# XMOS_TSBOARD_SPDIF.net
KiCad netlist of a schematic drawn in Altium Designer
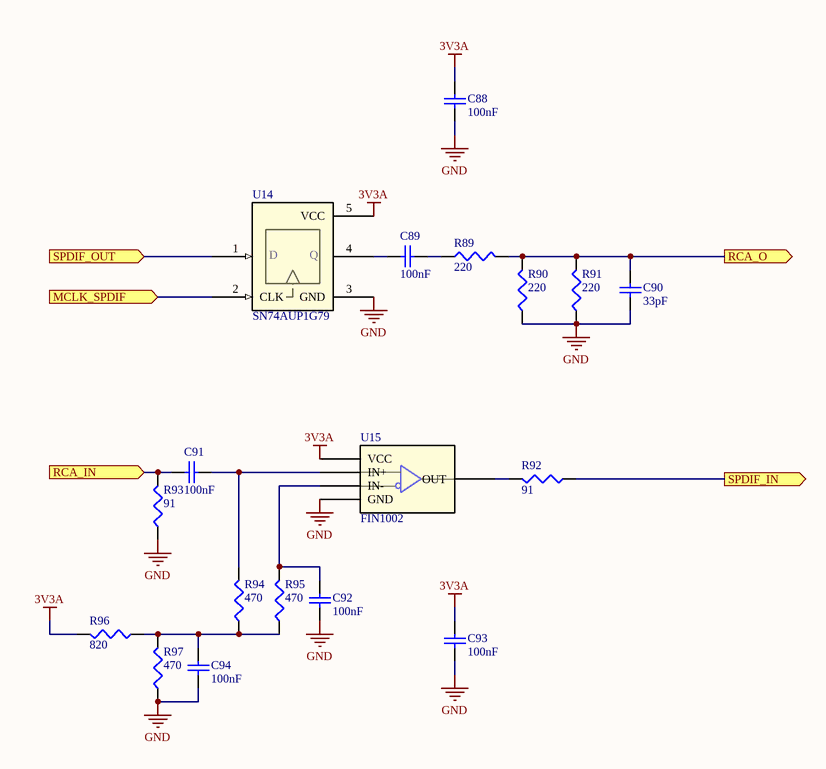
[diagram p0: XMOS_TSBOARD_SPDIF.SchDoc]

(export (version "E")
  (design (tool "Eeschema 10.0.6"))
  (components
    (comp (ref "C88")
      (value "100nF")
      (footprint "1608[0603]")
      (description "Capacitor (Semiconductor SIM Model)")
      (fields (field (name "Comment") "Cap Semi") (field (name "PUBLISHER") "Altium Limited"))
      (libsource (lib "Miscellaneous Devices") (part "Cap Semi"))
    )
    (comp (ref "C89")
      (value "100nF")
      (footprint "1608[0603]")
      (description "Capacitor (Semiconductor SIM Model)")
      (fields (field (name "Comment") "Cap Semi") (field (name "PUBLISHER") "Altium Limited"))
      (libsource (lib "Miscellaneous Devices") (part "Cap Semi"))
    )
    (comp (ref "C90")
      (value "33pF")
      (footprint "1608[0603]")
      (description "Capacitor (Semiconductor SIM Model)")
      (fields (field (name "Comment") "Cap Semi") (field (name "PUBLISHER") "Altium Limited"))
      (libsource (lib "Miscellaneous Devices") (part "Cap Semi"))
    )
    (comp (ref "C91")
      (value "100nF")
      (footprint "1608[0603]")
      (description "Capacitor (Semiconductor SIM Model)")
      (fields (field (name "Comment") "Cap Semi") (field (name "PUBLISHER") "Altium Limited"))
      (libsource (lib "Miscellaneous Devices") (part "Cap Semi"))
    )
    (comp (ref "C92")
      (value "100nF")
      (footprint "1608[0603]")
      (description "Capacitor (Semiconductor SIM Model)")
      (fields (field (name "Comment") "Cap Semi") (field (name "PUBLISHER") "Altium Limited"))
      (libsource (lib "Miscellaneous Devices") (part "Cap Semi"))
    )
    (comp (ref "C93")
      (value "100nF")
      (footprint "1608[0603]")
      (description "Capacitor (Semiconductor SIM Model)")
      (fields (field (name "Comment") "Cap Semi") (field (name "PUBLISHER") "Altium Limited"))
      (libsource (lib "Miscellaneous Devices") (part "Cap Semi"))
    )
    (comp (ref "C94")
      (value "100nF")
      (footprint "1608[0603]")
      (description "Capacitor (Semiconductor SIM Model)")
      (fields (field (name "Comment") "Cap Semi") (field (name "PUBLISHER") "Altium Limited"))
      (libsource (lib "Miscellaneous Devices") (part "Cap Semi"))
    )
    (comp (ref "R89")
      (value "220")
      (footprint "J1-0603")
      (description "Resistor")
      (fields (field (name "Comment") "Res3") (field (name "PUBLISHER") "Altium Limited"))
      (libsource (lib "Miscellaneous Devices") (part "Res3"))
    )
    (comp (ref "R90")
      (value "220")
      (footprint "J1-0603")
      (description "Resistor")
      (fields (field (name "Comment") "Res3") (field (name "PUBLISHER") "Altium Limited"))
      (libsource (lib "Miscellaneous Devices") (part "Res3"))
    )
    (comp (ref "R91")
      (value "220")
      (footprint "J1-0603")
      (description "Resistor")
      (fields (field (name "Comment") "Res3") (field (name "PUBLISHER") "Altium Limited"))
      (libsource (lib "Miscellaneous Devices") (part "Res3"))
    )
    (comp (ref "R92")
      (value "91")
      (footprint "J1-0603")
      (description "Resistor")
      (fields (field (name "Comment") "Res3") (field (name "PUBLISHER") "Altium Limited"))
      (libsource (lib "Miscellaneous Devices") (part "Res3"))
    )
    (comp (ref "R93")
      (value "91")
      (footprint "J1-0603")
      (description "Resistor")
      (fields (field (name "Comment") "Res3") (field (name "PUBLISHER") "Altium Limited"))
      (libsource (lib "Miscellaneous Devices") (part "Res3"))
    )
    (comp (ref "R94")
      (value "470")
      (footprint "J1-0603")
      (description "Resistor")
      (fields (field (name "Comment") "Res3") (field (name "PUBLISHER") "Altium Limited"))
      (libsource (lib "Miscellaneous Devices") (part "Res3"))
    )
    (comp (ref "R95")
      (value "470")
      (footprint "J1-0603")
      (description "Resistor")
      (fields (field (name "Comment") "Res3") (field (name "PUBLISHER") "Altium Limited"))
      (libsource (lib "Miscellaneous Devices") (part "Res3"))
    )
    (comp (ref "R96")
      (value "820")
      (footprint "J1-0603")
      (description "Resistor")
      (fields (field (name "Comment") "Res3") (field (name "PUBLISHER") "Altium Limited"))
      (libsource (lib "Miscellaneous Devices") (part "Res3"))
    )
    (comp (ref "R97")
      (value "470")
      (footprint "J1-0603")
      (description "Resistor")
      (fields (field (name "Comment") "Res3") (field (name "PUBLISHER") "Altium Limited"))
      (libsource (lib "Miscellaneous Devices") (part "Res3"))
    )
    (comp (ref "U14")
      (value "SN74AUP1G79")
      (footprint "DBV5")
      (description "Low-Power Single Positive-Edge-Triggered D-Type Flip-Flop")
      (libsource (lib "Troposphere_lib") (part "SN74AUP1G79"))
    )
    (comp (ref "U15")
      (value "FIN1002")
      (footprint "DBV5")
      (description "LVDS 1-Bit High Speed Differential Receiver")
      (libsource (lib "Troposphere_lib") (part "FIN1002"))
    )
  )
  (nets
    (net (code "1") (name "/MCLK_SPDIF") (class "Default")
      (node (ref "U14") (pin "2") (pinfunction "CLK_2") (pintype "input"))
    )
    (net (code "2") (name "/RCA_IN") (class "Default")
      (node (ref "C91") (pin "1") (pinfunction "1_1") (pintype "passive"))
      (node (ref "R93") (pin "2") (pinfunction "2_2") (pintype "passive"))
    )
    (net (code "3") (name "/RCA_O") (class "Default")
      (node (ref "C90") (pin "2") (pinfunction "2_2") (pintype "passive"))
      (node (ref "R89") (pin "2") (pinfunction "2_2") (pintype "passive"))
      (node (ref "R90") (pin "2") (pinfunction "2_2") (pintype "passive"))
      (node (ref "R91") (pin "2") (pinfunction "2_2") (pintype "passive"))
    )
    (net (code "4") (name "/SPDIF_IN") (class "Default")
      (node (ref "R92") (pin "1") (pinfunction "1_1") (pintype "passive"))
    )
    (net (code "5") (name "/SPDIF_OUT") (class "Default")
      (node (ref "U14") (pin "1") (pinfunction "D_1") (pintype "input"))
    )
    (net (code "6") (name "3V3A") (class "Default")
      (node (ref "C88") (pin "2") (pinfunction "2_2") (pintype "passive"))
      (node (ref "C93") (pin "2") (pinfunction "2_2") (pintype "passive"))
      (node (ref "R96") (pin "2") (pinfunction "2_2") (pintype "passive"))
      (node (ref "U14") (pin "5") (pinfunction "VCC_5") (pintype "power_in"))
      (node (ref "U15") (pin "1") (pinfunction "VCC_1") (pintype "power_in"))
    )
    (net (code "7") (name "GND") (class "Default")
      (node (ref "C88") (pin "1") (pinfunction "1_1") (pintype "passive"))
      (node (ref "C90") (pin "1") (pinfunction "1_1") (pintype "passive"))
      (node (ref "C92") (pin "1") (pinfunction "1_1") (pintype "passive"))
      (node (ref "C93") (pin "1") (pinfunction "1_1") (pintype "passive"))
      (node (ref "C94") (pin "1") (pinfunction "1_1") (pintype "passive"))
      (node (ref "R90") (pin "1") (pinfunction "1_1") (pintype "passive"))
      (node (ref "R91") (pin "1") (pinfunction "1_1") (pintype "passive"))
      (node (ref "R93") (pin "1") (pinfunction "1_1") (pintype "passive"))
      (node (ref "R97") (pin "1") (pinfunction "1_1") (pintype "passive"))
      (node (ref "U14") (pin "3") (pinfunction "GND_3") (pintype "power_in"))
      (node (ref "U15") (pin "2") (pinfunction "GND_2") (pintype "power_in"))
    )
    (net (code "8") (name "Net-(C89-Pad2)") (class "Default")
      (node (ref "C89") (pin "2") (pinfunction "2_2") (pintype "passive"))
      (node (ref "R89") (pin "1") (pinfunction "1_1") (pintype "passive"))
    )
    (net (code "9") (name "Net-(C94-Pad2)") (class "Default")
      (node (ref "C94") (pin "2") (pinfunction "2_2") (pintype "passive"))
      (node (ref "R94") (pin "1") (pinfunction "1_1") (pintype "passive"))
      (node (ref "R95") (pin "1") (pinfunction "1_1") (pintype "passive"))
      (node (ref "R96") (pin "1") (pinfunction "1_1") (pintype "passive"))
      (node (ref "R97") (pin "2") (pinfunction "2_2") (pintype "passive"))
    )
    (net (code "10") (name "Net-(U14-Q)") (class "Default")
      (node (ref "C89") (pin "1") (pinfunction "1_1") (pintype "passive"))
      (node (ref "U14") (pin "4") (pinfunction "Q_4") (pintype "power_in"))
    )
    (net (code "11") (name "Net-(U15-IN+)") (class "Default")
      (node (ref "C91") (pin "2") (pinfunction "2_2") (pintype "passive"))
      (node (ref "R94") (pin "2") (pinfunction "2_2") (pintype "passive"))
      (node (ref "U15") (pin "3") (pinfunction "IN+_3") (pintype "power_in"))
    )
    (net (code "12") (name "Net-(U15-IN-)") (class "Default")
      (node (ref "C92") (pin "2") (pinfunction "2_2") (pintype "passive"))
      (node (ref "R95") (pin "2") (pinfunction "2_2") (pintype "passive"))
      (node (ref "U15") (pin "4") (pinfunction "IN-_4") (pintype "power_in"))
    )
    (net (code "13") (name "Net-(U15-OUT)") (class "Default")
      (node (ref "R92") (pin "2") (pinfunction "2_2") (pintype "passive"))
      (node (ref "U15") (pin "5") (pinfunction "OUT_5") (pintype "power_in"))
    )
  )
)
